# ZynqPS.net
KiCad netlist of a schematic drawn in Altium Designer
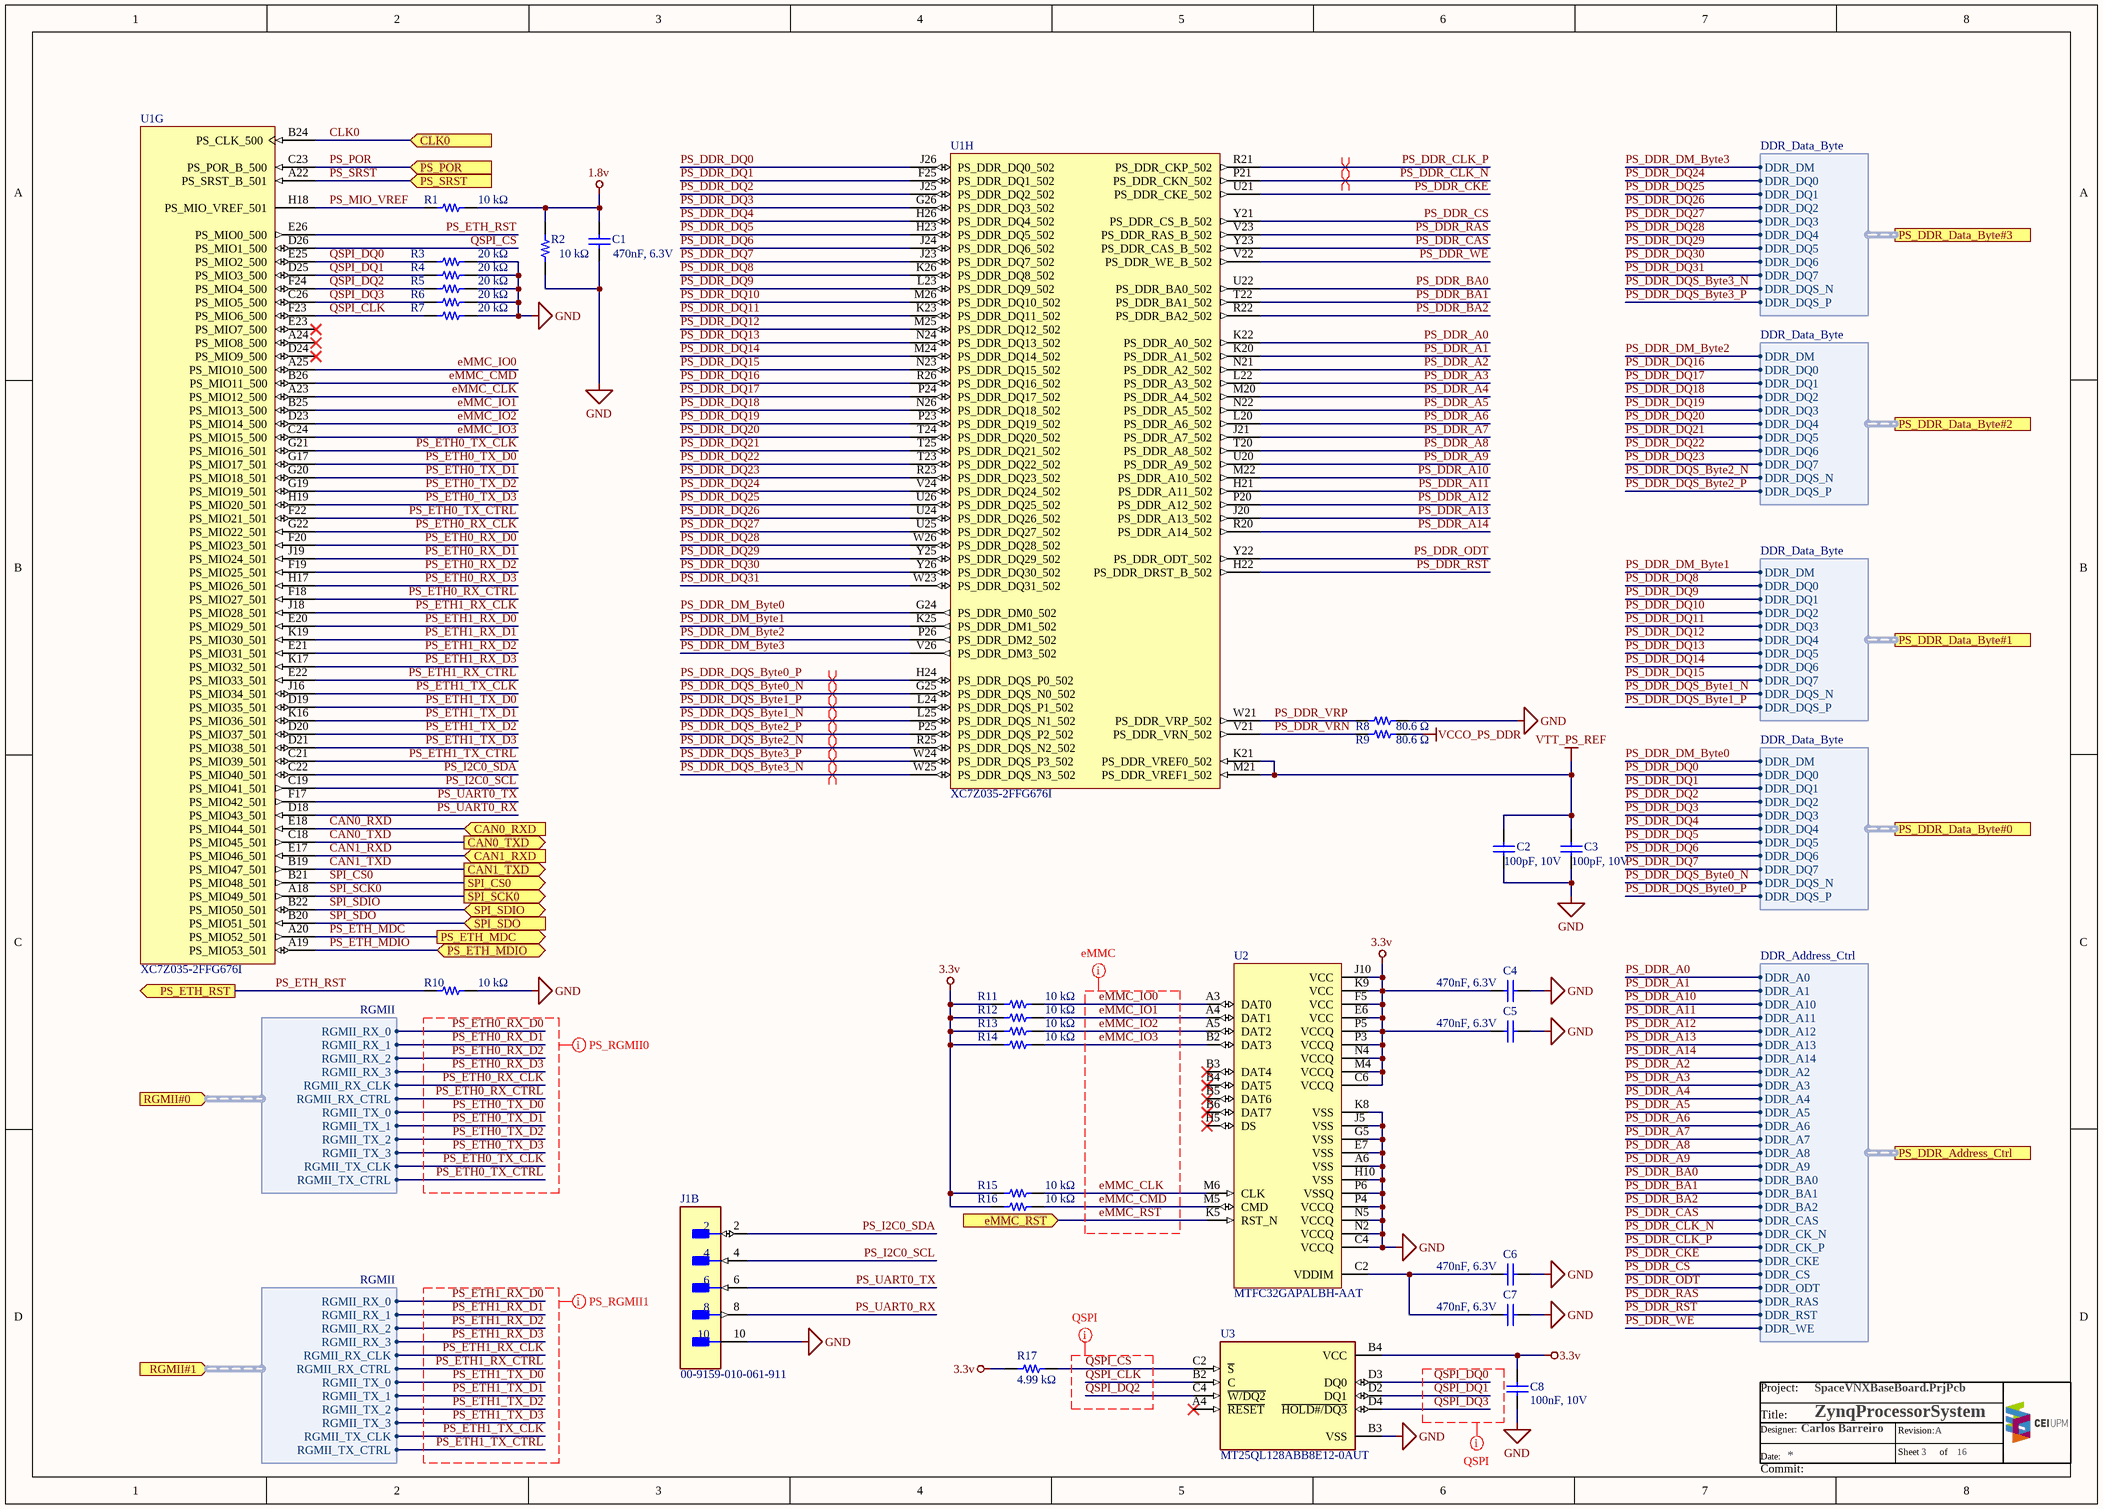
[diagram p0: ZynqPS.SchDoc]

(export (version "E")
  (design (tool "Eeschema 10.0.6"))
  (components
    (comp (ref "C1")
      (value "470nF, 6.3V")
      (footprint "WURTH_WCAP-CSGP_0402")
      (description "WCAP-CSGP Multilayer Ceramic Chip Capacitor, General Purpose, size 0402, X5R, 470nF, 6.3V")
      (fields
        (field (name "MANUFACTURER PART NUMBER") "885012105004")
        (field (name "MANUFACTURER") "Wurth Elektronik")
      )
      (libsource (lib "SpaceVNX") (part "885012105004"))
    )
    (comp (ref "C2")
      (value "100pF, 10V")
      (footprint "WURTH_WCAP-CSGP_0402")
      (description "WCAP-CSGP Multilayer Ceramic Chip Capacitor, General Purpose, size 0402, NP0, 100pF, 10V")
      (fields
        (field (name "MANUFACTURER PART NUMBER") "885012005013")
        (field (name "MANUFACTURER") "Wurth Elektronik")
      )
      (libsource (lib "SpaceVNX") (part "885012005013"))
    )
    (comp (ref "C3")
      (value "100pF, 10V")
      (footprint "WURTH_WCAP-CSGP_0402")
      (description "WCAP-CSGP Multilayer Ceramic Chip Capacitor, General Purpose, size 0402, NP0, 100pF, 10V")
      (fields
        (field (name "MANUFACTURER PART NUMBER") "885012005013")
        (field (name "MANUFACTURER") "Wurth Elektronik")
      )
      (libsource (lib "SpaceVNX") (part "885012005013"))
    )
    (comp (ref "C4")
      (value "470nF, 6.3V")
      (footprint "WURTH_WCAP-CSGP_0402")
      (description "WCAP-CSGP Multilayer Ceramic Chip Capacitor, General Purpose, size 0402, X5R, 470nF, 6.3V")
      (fields
        (field (name "MANUFACTURER PART NUMBER") "885012105004")
        (field (name "MANUFACTURER") "Wurth Elektronik")
      )
      (libsource (lib "SpaceVNX") (part "885012105004"))
    )
    (comp (ref "C5")
      (value "470nF, 6.3V")
      (footprint "WURTH_WCAP-CSGP_0402")
      (description "WCAP-CSGP Multilayer Ceramic Chip Capacitor, General Purpose, size 0402, X5R, 470nF, 6.3V")
      (fields
        (field (name "MANUFACTURER PART NUMBER") "885012105004")
        (field (name "MANUFACTURER") "Wurth Elektronik")
      )
      (libsource (lib "SpaceVNX") (part "885012105004"))
    )
    (comp (ref "C6")
      (value "470nF, 6.3V")
      (footprint "WURTH_WCAP-CSGP_0402")
      (description "WCAP-CSGP Multilayer Ceramic Chip Capacitor, General Purpose, size 0402, X5R, 470nF, 6.3V")
      (fields
        (field (name "MANUFACTURER PART NUMBER") "885012105004")
        (field (name "MANUFACTURER") "Wurth Elektronik")
      )
      (libsource (lib "SpaceVNX") (part "885012105004"))
    )
    (comp (ref "C7")
      (value "470nF, 6.3V")
      (footprint "WURTH_WCAP-CSGP_0402")
      (description "WCAP-CSGP Multilayer Ceramic Chip Capacitor, General Purpose, size 0402, X5R, 470nF, 6.3V")
      (fields
        (field (name "MANUFACTURER PART NUMBER") "885012105004")
        (field (name "MANUFACTURER") "Wurth Elektronik")
      )
      (libsource (lib "SpaceVNX") (part "885012105004"))
    )
    (comp (ref "C8")
      (value "100nF, 10V")
      (footprint "WURTH_WCAP-CSGP_0402")
      (description "WCAP-CSGP Multilayer Ceramic Chip Capacitor, General Purpose, size 0402, X7R, 100nF, 10V")
      (fields
        (field (name "MANUFACTURER PART NUMBER") "885012205018")
        (field (name "MANUFACTURER") "Wurth Elektronik")
      )
      (libsource (lib "SpaceVNX") (part "885012205018"))
    )
    (comp (ref "J1")
      (value "00-9159-010-061-911")
      (footprint "KYOCERA_00-9159-010-061-911")
      (description "Coplanar Open Ended Card Edge Connector 10 Pin")
      (libsource (lib "SpaceVNX") (part "00-9159-010-061-911"))
    )
    (comp (ref "R1")
      (value "10 kΩ")
      (footprint "PANASONIC_ERJ2G_0402")
      (description "General Purpose Thick Film Chip Resistors")
      (fields (field (name "MANUFACTURER") "Panasonic"))
      (libsource (lib "SpaceVNX") (part "ERJ2RKF1002X"))
    )
    (comp (ref "R2")
      (value "10 kΩ")
      (footprint "PANASONIC_ERJ2G_0402")
      (description "General Purpose Thick Film Chip Resistors")
      (fields (field (name "MANUFACTURER") "Panasonic"))
      (libsource (lib "SpaceVNX") (part "ERJ2RKF1002X"))
    )
    (comp (ref "R3")
      (value "20 kΩ")
      (footprint "PANASONIC_ERJ2G_0402")
      (description "General Purpose Thick Film Chip Resistors")
      (fields (field (name "MANUFACTURER") "Panasonic"))
      (libsource (lib "SpaceVNX") (part "ERJ2RKF2002X"))
    )
    (comp (ref "R4")
      (value "20 kΩ")
      (footprint "PANASONIC_ERJ2G_0402")
      (description "General Purpose Thick Film Chip Resistors")
      (fields (field (name "MANUFACTURER") "Panasonic"))
      (libsource (lib "SpaceVNX") (part "ERJ2RKF2002X"))
    )
    (comp (ref "R5")
      (value "20 kΩ")
      (footprint "PANASONIC_ERJ2G_0402")
      (description "General Purpose Thick Film Chip Resistors")
      (fields (field (name "MANUFACTURER") "Panasonic"))
      (libsource (lib "SpaceVNX") (part "ERJ2RKF2002X"))
    )
    (comp (ref "R6")
      (value "20 kΩ")
      (footprint "PANASONIC_ERJ2G_0402")
      (description "General Purpose Thick Film Chip Resistors")
      (fields (field (name "MANUFACTURER") "Panasonic"))
      (libsource (lib "SpaceVNX") (part "ERJ2RKF2002X"))
    )
    (comp (ref "R7")
      (value "20 kΩ")
      (footprint "PANASONIC_ERJ2G_0402")
      (description "General Purpose Thick Film Chip Resistors")
      (fields (field (name "MANUFACTURER") "Panasonic"))
      (libsource (lib "SpaceVNX") (part "ERJ2RKF2002X"))
    )
    (comp (ref "R8")
      (value "80.6 Ω")
      (footprint "PANASONIC_ERJ2G_0402")
      (description "General Purpose Thick Film Chip Resistors")
      (fields (field (name "MANUFACTURER") "Panasonic"))
      (libsource (lib "SpaceVNX") (part "ERJ2RKF80R6X"))
    )
    (comp (ref "R9")
      (value "80.6 Ω")
      (footprint "PANASONIC_ERJ2G_0402")
      (description "General Purpose Thick Film Chip Resistors")
      (fields (field (name "MANUFACTURER") "Panasonic"))
      (libsource (lib "SpaceVNX") (part "ERJ2RKF80R6X"))
    )
    (comp (ref "R10")
      (value "10 kΩ")
      (footprint "PANASONIC_ERJ2G_0402")
      (description "General Purpose Thick Film Chip Resistors")
      (fields (field (name "MANUFACTURER") "Panasonic"))
      (libsource (lib "SpaceVNX") (part "ERJ2RKF1002X"))
    )
    (comp (ref "R11")
      (value "10 kΩ")
      (footprint "PANASONIC_ERJ2G_0402")
      (description "General Purpose Thick Film Chip Resistors")
      (fields (field (name "MANUFACTURER") "Panasonic"))
      (libsource (lib "SpaceVNX") (part "ERJ2RKF1002X"))
    )
    (comp (ref "R12")
      (value "10 kΩ")
      (footprint "PANASONIC_ERJ2G_0402")
      (description "General Purpose Thick Film Chip Resistors")
      (fields (field (name "MANUFACTURER") "Panasonic"))
      (libsource (lib "SpaceVNX") (part "ERJ2RKF1002X"))
    )
    (comp (ref "R13")
      (value "10 kΩ")
      (footprint "PANASONIC_ERJ2G_0402")
      (description "General Purpose Thick Film Chip Resistors")
      (fields (field (name "MANUFACTURER") "Panasonic"))
      (libsource (lib "SpaceVNX") (part "ERJ2RKF1002X"))
    )
    (comp (ref "R14")
      (value "10 kΩ")
      (footprint "PANASONIC_ERJ2G_0402")
      (description "General Purpose Thick Film Chip Resistors")
      (fields (field (name "MANUFACTURER") "Panasonic"))
      (libsource (lib "SpaceVNX") (part "ERJ2RKF1002X"))
    )
    (comp (ref "R15")
      (value "10 kΩ")
      (footprint "PANASONIC_ERJ2G_0402")
      (description "General Purpose Thick Film Chip Resistors")
      (fields (field (name "MANUFACTURER") "Panasonic"))
      (libsource (lib "SpaceVNX") (part "ERJ2RKF1002X"))
    )
    (comp (ref "R16")
      (value "10 kΩ")
      (footprint "PANASONIC_ERJ2G_0402")
      (description "General Purpose Thick Film Chip Resistors")
      (fields (field (name "MANUFACTURER") "Panasonic"))
      (libsource (lib "SpaceVNX") (part "ERJ2RKF1002X"))
    )
    (comp (ref "R17")
      (value "4.99 kΩ")
      (footprint "PANASONIC_ERJ2G_0402")
      (description "General Purpose Thick Film Chip Resistors")
      (fields (field (name "MANUFACTURER") "Panasonic"))
      (libsource (lib "SpaceVNX") (part "ERJ2RKF4991X"))
    )
    (comp (ref "U1")
      (value "XC7Z035-2FFG676I")
      (footprint "XILINX_FBG676")
      (fields (field (name "PARTNUMBER") "XC7Z035-2FBG676I") (field (name "GENERIC PART NUMBER") "XC7Z035"))
      (libsource (lib "SpaceVNX") (part "XC7Z035-2FFG676I"))
    )
    (comp (ref "U2")
      (value "MTFC32GAPALBH-AAT")
      (footprint "Micron_BH")
      (description "Flash Memory Managed NAND e.MMC Automotive 32GB")
      (fields (field (name "MF") "Micron Technology"))
      (libsource (lib "SpaceVNX") (part "MTFC32GAPALBH-AAT"))
    )
    (comp (ref "U3")
      (value "MT25QL128ABB8E12-0AUT")
      (footprint "Micron_RW")
      (description "NOR Serial Flash Memory 128Mb 3.3V Multiple I/O Automotive")
      (fields (field (name "MF") "Micron Technology"))
      (libsource (lib "SpaceVNX") (part "MT25QL128ABB8E12-0AUT"))
    )
  )
  (nets
    (net (code "4") (name "/CAN0_RXD") (class "Default")
      (node (ref "U1") (pin "E18") (pinfunction "PS_MIO44_501_E18") (pintype "input"))
    )
    (net (code "5") (name "/CAN0_TXD") (class "Default")
      (node (ref "U1") (pin "C18") (pinfunction "PS_MIO45_501_C18") (pintype "output"))
    )
    (net (code "6") (name "/CAN1_RXD") (class "Default")
      (node (ref "U1") (pin "E17") (pinfunction "PS_MIO46_501_E17") (pintype "input"))
    )
    (net (code "7") (name "/CAN1_TXD") (class "Default")
      (node (ref "U1") (pin "B19") (pinfunction "PS_MIO47_501_B19") (pintype "output"))
    )
    (net (code "8") (name "/CLK0") (class "Default")
      (node (ref "U1") (pin "B24") (pinfunction "PS_CLK_500_B24") (pintype "input"))
    )
    (net (code "9") (name "/PS_DDR_A0") (class "Default")
      (node (ref "U1") (pin "K22") (pinfunction "PS_DDR_A0_502_K22") (pintype "output"))
    )
    (net (code "10") (name "/PS_DDR_A1") (class "Default")
      (node (ref "U1") (pin "K20") (pinfunction "PS_DDR_A1_502_K20") (pintype "output"))
    )
    (net (code "11") (name "/PS_DDR_A2") (class "Default")
      (node (ref "U1") (pin "N21") (pinfunction "PS_DDR_A2_502_N21") (pintype "output"))
    )
    (net (code "12") (name "/PS_DDR_A3") (class "Default")
      (node (ref "U1") (pin "L22") (pinfunction "PS_DDR_A3_502_L22") (pintype "output"))
    )
    (net (code "13") (name "/PS_DDR_A4") (class "Default")
      (node (ref "U1") (pin "M20") (pinfunction "PS_DDR_A4_502_M20") (pintype "output"))
    )
    (net (code "14") (name "/PS_DDR_A5") (class "Default")
      (node (ref "U1") (pin "N22") (pinfunction "PS_DDR_A5_502_N22") (pintype "output"))
    )
    (net (code "15") (name "/PS_DDR_A6") (class "Default")
      (node (ref "U1") (pin "L20") (pinfunction "PS_DDR_A6_502_L20") (pintype "output"))
    )
    (net (code "16") (name "/PS_DDR_A7") (class "Default")
      (node (ref "U1") (pin "J21") (pinfunction "PS_DDR_A7_502_J21") (pintype "output"))
    )
    (net (code "17") (name "/PS_DDR_A8") (class "Default")
      (node (ref "U1") (pin "T20") (pinfunction "PS_DDR_A8_502_T20") (pintype "output"))
    )
    (net (code "18") (name "/PS_DDR_A9") (class "Default")
      (node (ref "U1") (pin "U20") (pinfunction "PS_DDR_A9_502_U20") (pintype "output"))
    )
    (net (code "19") (name "/PS_DDR_A10") (class "Default")
      (node (ref "U1") (pin "M22") (pinfunction "PS_DDR_A10_502_M22") (pintype "output"))
    )
    (net (code "20") (name "/PS_DDR_A11") (class "Default")
      (node (ref "U1") (pin "H21") (pinfunction "PS_DDR_A11_502_H21") (pintype "output"))
    )
    (net (code "21") (name "/PS_DDR_A12") (class "Default")
      (node (ref "U1") (pin "P20") (pinfunction "PS_DDR_A12_502_P20") (pintype "output"))
    )
    (net (code "22") (name "/PS_DDR_A13") (class "Default")
      (node (ref "U1") (pin "J20") (pinfunction "PS_DDR_A13_502_J20") (pintype "output"))
    )
    (net (code "23") (name "/PS_DDR_A14") (class "Default")
      (node (ref "U1") (pin "R20") (pinfunction "PS_DDR_A14_502_R20") (pintype "output"))
    )
    (net (code "24") (name "/PS_DDR_BA0") (class "Default")
      (node (ref "U1") (pin "U22") (pinfunction "PS_DDR_BA0_502_U22") (pintype "output"))
    )
    (net (code "25") (name "/PS_DDR_BA1") (class "Default")
      (node (ref "U1") (pin "T22") (pinfunction "PS_DDR_BA1_502_T22") (pintype "output"))
    )
    (net (code "26") (name "/PS_DDR_BA2") (class "Default")
      (node (ref "U1") (pin "R22") (pinfunction "PS_DDR_BA2_502_R22") (pintype "output"))
    )
    (net (code "27") (name "/PS_DDR_CAS") (class "Default")
      (node (ref "U1") (pin "Y23") (pinfunction "PS_DDR_CAS_B_502_Y23") (pintype "output"))
    )
    (net (code "28") (name "/PS_DDR_CKE") (class "Default")
      (node (ref "U1") (pin "U21") (pinfunction "PS_DDR_CKE_502_U21") (pintype "output"))
    )
    (net (code "29") (name "/PS_DDR_CLK_N") (class "Default")
      (node (ref "U1") (pin "P21") (pinfunction "PS_DDR_CKN_502_P21") (pintype "output"))
    )
    (net (code "30") (name "/PS_DDR_CLK_P") (class "Default")
      (node (ref "U1") (pin "R21") (pinfunction "PS_DDR_CKP_502_R21") (pintype "output"))
    )
    (net (code "31") (name "/PS_DDR_CS") (class "Default")
      (node (ref "U1") (pin "Y21") (pinfunction "PS_DDR_CS_B_502_Y21") (pintype "output"))
    )
    (net (code "32") (name "/PS_DDR_DM_Byte0") (class "Default")
      (node (ref "U1") (pin "G24") (pinfunction "PS_DDR_DM0_502_G24") (pintype "output"))
    )
    (net (code "33") (name "/PS_DDR_DM_Byte1") (class "Default")
      (node (ref "U1") (pin "K25") (pinfunction "PS_DDR_DM1_502_K25") (pintype "output"))
    )
    (net (code "34") (name "/PS_DDR_DM_Byte2") (class "Default")
      (node (ref "U1") (pin "P26") (pinfunction "PS_DDR_DM2_502_P26") (pintype "output"))
    )
    (net (code "35") (name "/PS_DDR_DM_Byte3") (class "Default")
      (node (ref "U1") (pin "V26") (pinfunction "PS_DDR_DM3_502_V26") (pintype "output"))
    )
    (net (code "36") (name "/PS_DDR_DQ0") (class "Default")
      (node (ref "U1") (pin "J26") (pinfunction "PS_DDR_DQ0_502_J26") (pintype "bidirectional"))
    )
    (net (code "37") (name "/PS_DDR_DQ1") (class "Default")
      (node (ref "U1") (pin "F25") (pinfunction "PS_DDR_DQ1_502_F25") (pintype "bidirectional"))
    )
    (net (code "38") (name "/PS_DDR_DQ2") (class "Default")
      (node (ref "U1") (pin "J25") (pinfunction "PS_DDR_DQ2_502_J25") (pintype "bidirectional"))
    )
    (net (code "39") (name "/PS_DDR_DQ3") (class "Default")
      (node (ref "U1") (pin "G26") (pinfunction "PS_DDR_DQ3_502_G26") (pintype "bidirectional"))
    )
    (net (code "40") (name "/PS_DDR_DQ4") (class "Default")
      (node (ref "U1") (pin "H26") (pinfunction "PS_DDR_DQ4_502_H26") (pintype "bidirectional"))
    )
    (net (code "41") (name "/PS_DDR_DQ5") (class "Default")
      (node (ref "U1") (pin "H23") (pinfunction "PS_DDR_DQ5_502_H23") (pintype "bidirectional"))
    )
    (net (code "42") (name "/PS_DDR_DQ6") (class "Default")
      (node (ref "U1") (pin "J24") (pinfunction "PS_DDR_DQ6_502_J24") (pintype "bidirectional"))
    )
    (net (code "43") (name "/PS_DDR_DQ7") (class "Default")
      (node (ref "U1") (pin "J23") (pinfunction "PS_DDR_DQ7_502_J23") (pintype "bidirectional"))
    )
    (net (code "44") (name "/PS_DDR_DQ8") (class "Default")
      (node (ref "U1") (pin "K26") (pinfunction "PS_DDR_DQ8_502_K26") (pintype "bidirectional"))
    )
    (net (code "45") (name "/PS_DDR_DQ9") (class "Default")
      (node (ref "U1") (pin "L23") (pinfunction "PS_DDR_DQ9_502_L23") (pintype "bidirectional"))
    )
    (net (code "46") (name "/PS_DDR_DQ10") (class "Default")
      (node (ref "U1") (pin "M26") (pinfunction "PS_DDR_DQ10_502_M26") (pintype "bidirectional"))
    )
    (net (code "47") (name "/PS_DDR_DQ11") (class "Default")
      (node (ref "U1") (pin "K23") (pinfunction "PS_DDR_DQ11_502_K23") (pintype "bidirectional"))
    )
    (net (code "48") (name "/PS_DDR_DQ12") (class "Default")
      (node (ref "U1") (pin "M25") (pinfunction "PS_DDR_DQ12_502_M25") (pintype "bidirectional"))
    )
    (net (code "49") (name "/PS_DDR_DQ13") (class "Default")
      (node (ref "U1") (pin "N24") (pinfunction "PS_DDR_DQ13_502_N24") (pintype "bidirectional"))
    )
    (net (code "50") (name "/PS_DDR_DQ14") (class "Default")
      (node (ref "U1") (pin "M24") (pinfunction "PS_DDR_DQ14_502_M24") (pintype "bidirectional"))
    )
    (net (code "51") (name "/PS_DDR_DQ15") (class "Default")
      (node (ref "U1") (pin "N23") (pinfunction "PS_DDR_DQ15_502_N23") (pintype "bidirectional"))
    )
    (net (code "52") (name "/PS_DDR_DQ16") (class "Default")
      (node (ref "U1") (pin "R26") (pinfunction "PS_DDR_DQ16_502_R26") (pintype "bidirectional"))
    )
    (net (code "53") (name "/PS_DDR_DQ17") (class "Default")
      (node (ref "U1") (pin "P24") (pinfunction "PS_DDR_DQ17_502_P24") (pintype "bidirectional"))
    )
    (net (code "54") (name "/PS_DDR_DQ18") (class "Default")
      (node (ref "U1") (pin "N26") (pinfunction "PS_DDR_DQ18_502_N26") (pintype "bidirectional"))
    )
    (net (code "55") (name "/PS_DDR_DQ19") (class "Default")
      (node (ref "U1") (pin "P23") (pinfunction "PS_DDR_DQ19_502_P23") (pintype "bidirectional"))
    )
    (net (code "56") (name "/PS_DDR_DQ20") (class "Default")
      (node (ref "U1") (pin "T24") (pinfunction "PS_DDR_DQ20_502_T24") (pintype "bidirectional"))
    )
    (net (code "57") (name "/PS_DDR_DQ21") (class "Default")
      (node (ref "U1") (pin "T25") (pinfunction "PS_DDR_DQ21_502_T25") (pintype "bidirectional"))
    )
    (net (code "58") (name "/PS_DDR_DQ22") (class "Default")
      (node (ref "U1") (pin "T23") (pinfunction "PS_DDR_DQ22_502_T23") (pintype "bidirectional"))
    )
    (net (code "59") (name "/PS_DDR_DQ23") (class "Default")
      (node (ref "U1") (pin "R23") (pinfunction "PS_DDR_DQ23_502_R23") (pintype "bidirectional"))
    )
    (net (code "60") (name "/PS_DDR_DQ24") (class "Default")
      (node (ref "U1") (pin "V24") (pinfunction "PS_DDR_DQ24_502_V24") (pintype "bidirectional"))
    )
    (net (code "61") (name "/PS_DDR_DQ25") (class "Default")
      (node (ref "U1") (pin "U26") (pinfunction "PS_DDR_DQ25_502_U26") (pintype "bidirectional"))
    )
    (net (code "62") (name "/PS_DDR_DQ26") (class "Default")
      (node (ref "U1") (pin "U24") (pinfunction "PS_DDR_DQ26_502_U24") (pintype "bidirectional"))
    )
    (net (code "63") (name "/PS_DDR_DQ27") (class "Default")
      (node (ref "U1") (pin "U25") (pinfunction "PS_DDR_DQ27_502_U25") (pintype "bidirectional"))
    )
    (net (code "64") (name "/PS_DDR_DQ28") (class "Default")
      (node (ref "U1") (pin "W26") (pinfunction "PS_DDR_DQ28_502_W26") (pintype "bidirectional"))
    )
    (net (code "65") (name "/PS_DDR_DQ29") (class "Default")
      (node (ref "U1") (pin "Y25") (pinfunction "PS_DDR_DQ29_502_Y25") (pintype "bidirectional"))
    )
    (net (code "66") (name "/PS_DDR_DQ30") (class "Default")
      (node (ref "U1") (pin "Y26") (pinfunction "PS_DDR_DQ30_502_Y26") (pintype "bidirectional"))
    )
    (net (code "67") (name "/PS_DDR_DQ31") (class "Default")
      (node (ref "U1") (pin "W23") (pinfunction "PS_DDR_DQ31_502_W23") (pintype "bidirectional"))
    )
    (net (code "68") (name "/PS_DDR_DQS_Byte0_N") (class "Default")
      (node (ref "U1") (pin "G25") (pinfunction "PS_DDR_DQS_N0_502_G25") (pintype "bidirectional"))
    )
    (net (code "69") (name "/PS_DDR_DQS_Byte0_P") (class "Default")
      (node (ref "U1") (pin "H24") (pinfunction "PS_DDR_DQS_P0_502_H24") (pintype "bidirectional"))
    )
    (net (code "70") (name "/PS_DDR_DQS_Byte1_N") (class "Default")
      (node (ref "U1") (pin "L25") (pinfunction "PS_DDR_DQS_N1_502_L25") (pintype "bidirectional"))
    )
    (net (code "71") (name "/PS_DDR_DQS_Byte1_P") (class "Default")
      (node (ref "U1") (pin "L24") (pinfunction "PS_DDR_DQS_P1_502_L24") (pintype "bidirectional"))
    )
    (net (code "72") (name "/PS_DDR_DQS_Byte2_N") (class "Default")
      (node (ref "U1") (pin "R25") (pinfunction "PS_DDR_DQS_N2_502_R25") (pintype "bidirectional"))
    )
    (net (code "73") (name "/PS_DDR_DQS_Byte2_P") (class "Default")
      (node (ref "U1") (pin "P25") (pinfunction "PS_DDR_DQS_P2_502_P25") (pintype "bidirectional"))
    )
    (net (code "74") (name "/PS_DDR_DQS_Byte3_N") (class "Default")
      (node (ref "U1") (pin "W25") (pinfunction "PS_DDR_DQS_N3_502_W25") (pintype "bidirectional"))
    )
    (net (code "75") (name "/PS_DDR_DQS_Byte3_P") (class "Default")
      (node (ref "U1") (pin "W24") (pinfunction "PS_DDR_DQS_P3_502_W24") (pintype "bidirectional"))
    )
    (net (code "76") (name "/PS_DDR_ODT") (class "Default")
      (node (ref "U1") (pin "Y22") (pinfunction "PS_DDR_ODT_502_Y22") (pintype "output"))
    )
    (net (code "77") (name "/PS_DDR_RAS") (class "Default")
      (node (ref "U1") (pin "V23") (pinfunction "PS_DDR_RAS_B_502_V23") (pintype "output"))
    )
    (net (code "78") (name "/PS_DDR_RST") (class "Default")
      (node (ref "U1") (pin "H22") (pinfunction "PS_DDR_DRST_B_502_H22") (pintype "output"))
    )
    (net (code "79") (name "/PS_DDR_VRN") (class "Default")
      (node (ref "R9") (pin "1") (pinfunction "1_1") (pintype "passive"))
      (node (ref "U1") (pin "V21") (pinfunction "PS_DDR_VRN_502_V21") (pintype "output"))
    )
    (net (code "80") (name "/PS_DDR_VRP") (class "Default")
      (node (ref "R8") (pin "1") (pinfunction "1_1") (pintype "passive"))
      (node (ref "U1") (pin "W21") (pinfunction "PS_DDR_VRP_502_W21") (pintype "output"))
    )
    (net (code "81") (name "/PS_DDR_WE") (class "Default")
      (node (ref "U1") (pin "V22") (pinfunction "PS_DDR_WE_B_502_V22") (pintype "output"))
    )
    (net (code "82") (name "/PS_ETH0_RX_CLK") (class "Default")
      (node (ref "U1") (pin "G22") (pinfunction "PS_MIO22_501_G22") (pintype "input"))
    )
    (net (code "83") (name "/PS_ETH0_RX_CTRL") (class "Default")
      (node (ref "U1") (pin "F18") (pinfunction "PS_MIO27_501_F18") (pintype "input"))
    )
    (net (code "84") (name "/PS_ETH0_RX_D0") (class "Default")
      (node (ref "U1") (pin "F20") (pinfunction "PS_MIO23_501_F20") (pintype "input"))
    )
    (net (code "85") (name "/PS_ETH0_RX_D1") (class "Default")
      (node (ref "U1") (pin "J19") (pinfunction "PS_MIO24_501_J19") (pintype "input"))
    )
    (net (code "86") (name "/PS_ETH0_RX_D2") (class "Default")
      (node (ref "U1") (pin "F19") (pinfunction "PS_MIO25_501_F19") (pintype "input"))
    )
    (net (code "87") (name "/PS_ETH0_RX_D3") (class "Default")
      (node (ref "U1") (pin "H17") (pinfunction "PS_MIO26_501_H17") (pintype "input"))
    )
    (net (code "88") (name "/PS_ETH0_TX_CLK") (class "Default")
      (node (ref "U1") (pin "G21") (pinfunction "PS_MIO16_501_G21") (pintype "bidirectional"))
    )
    (net (code "89") (name "/PS_ETH0_TX_CTRL") (class "Default")
      (node (ref "U1") (pin "F22") (pinfunction "PS_MIO21_501_F22") (pintype "bidirectional"))
    )
    (net (code "90") (name "/PS_ETH0_TX_D0") (class "Default")
      (node (ref "U1") (pin "G17") (pinfunction "PS_MIO17_501_G17") (pintype "bidirectional"))
    )
    (net (code "91") (name "/PS_ETH0_TX_D1") (class "Default")
      (node (ref "U1") (pin "G20") (pinfunction "PS_MIO18_501_G20") (pintype "bidirectional"))
    )
    (net (code "92") (name "/PS_ETH0_TX_D2") (class "Default")
      (node (ref "U1") (pin "G19") (pinfunction "PS_MIO19_501_G19") (pintype "bidirectional"))
    )
    (net (code "93") (name "/PS_ETH0_TX_D3") (class "Default")
      (node (ref "U1") (pin "H19") (pinfunction "PS_MIO20_501_H19") (pintype "bidirectional"))
    )
    (net (code "94") (name "/PS_ETH1_RX_CLK") (class "Default")
      (node (ref "U1") (pin "J18") (pinfunction "PS_MIO28_501_J18") (pintype "input"))
    )
    (net (code "95") (name "/PS_ETH1_RX_CTRL") (class "Default")
      (node (ref "U1") (pin "E22") (pinfunction "PS_MIO33_501_E22") (pintype "input"))
    )
    (net (code "96") (name "/PS_ETH1_RX_D0") (class "Default")
      (node (ref "U1") (pin "E20") (pinfunction "PS_MIO29_501_E20") (pintype "input"))
    )
    (net (code "97") (name "/PS_ETH1_RX_D1") (class "Default")
      (node (ref "U1") (pin "K19") (pinfunction "PS_MIO30_501_K19") (pintype "input"))
    )
    (net (code "98") (name "/PS_ETH1_RX_D2") (class "Default")
      (node (ref "U1") (pin "E21") (pinfunction "PS_MIO31_501_E21") (pintype "input"))
    )
    (net (code "99") (name "/PS_ETH1_RX_D3") (class "Default")
      (node (ref "U1") (pin "K17") (pinfunction "PS_MIO32_501_K17") (pintype "input"))
    )
    (net (code "100") (name "/PS_ETH1_TX_CLK") (class "Default")
      (node (ref "U1") (pin "J16") (pinfunction "PS_MIO34_501_J16") (pintype "bidirectional"))
    )
    (net (code "101") (name "/PS_ETH1_TX_CTRL") (class "Default")
      (node (ref "U1") (pin "C21") (pinfunction "PS_MIO39_501_C21") (pintype "bidirectional"))
    )
    (net (code "102") (name "/PS_ETH1_TX_D0") (class "Default")
      (node (ref "U1") (pin "D19") (pinfunction "PS_MIO35_501_D19") (pintype "bidirectional"))
    )
    (net (code "103") (name "/PS_ETH1_TX_D1") (class "Default")
      (node (ref "U1") (pin "K16") (pinfunction "PS_MIO36_501_K16") (pintype "bidirectional"))
    )
    (net (code "104") (name "/PS_ETH1_TX_D2") (class "Default")
      (node (ref "U1") (pin "D20") (pinfunction "PS_MIO37_501_D20") (pintype "bidirectional"))
    )
    (net (code "105") (name "/PS_ETH1_TX_D3") (class "Default")
      (node (ref "U1") (pin "D21") (pinfunction "PS_MIO38_501_D21") (pintype "bidirectional"))
    )
    (net (code "106") (name "/PS_ETH_MDC") (class "Default")
      (node (ref "U1") (pin "A20") (pinfunction "PS_MIO52_501_A20") (pintype "output"))
    )
    (net (code "107") (name "/PS_ETH_MDIO") (class "Default")
      (node (ref "U1") (pin "A19") (pinfunction "PS_MIO53_501_A19") (pintype "bidirectional"))
    )
    (net (code "108") (name "/PS_ETH_RST") (class "Default")
      (node (ref "R10") (pin "2") (pinfunction "2_2") (pintype "passive"))
      (node (ref "U1") (pin "E26") (pinfunction "PS_MIO0_500_E26") (pintype "output"))
    )
    (net (code "109") (name "/PS_I2C0_SCL") (class "Default")
      (node (ref "J1") (pin "4") (pinfunction "4_4") (pintype "input"))
      (node (ref "U1") (pin "C19") (pinfunction "PS_MIO41_501_C19") (pintype "output"))
    )
    (net (code "110") (name "/PS_I2C0_SDA") (class "Default")
      (node (ref "J1") (pin "2") (pinfunction "2_2") (pintype "bidirectional"))
      (node (ref "U1") (pin "C22") (pinfunction "PS_MIO40_501_C22") (pintype "bidirectional"))
    )
    (net (code "111") (name "/PS_MIO_VREF") (class "Default")
      (node (ref "R1") (pin "2") (pinfunction "2_2") (pintype "passive"))
      (node (ref "U1") (pin "H18") (pinfunction "PS_MIO_VREF_501_H18") (pintype "passive"))
    )
    (net (code "112") (name "/PS_POR") (class "Default")
      (node (ref "U1") (pin "C23") (pinfunction "PS_POR_B_500_C23") (pintype "input"))
    )
    (net (code "113") (name "/PS_SRST") (class "Default")
      (node (ref "U1") (pin "A22") (pinfunction "PS_SRST_B_501_A22") (pintype "input"))
    )
    (net (code "114") (name "/PS_UART0_RX") (class "Default")
      (node (ref "J1") (pin "8") (pinfunction "8_8") (pintype "output"))
      (node (ref "U1") (pin "D18") (pinfunction "PS_MIO43_501_D18") (pintype "input"))
    )
    (net (code "115") (name "/PS_UART0_TX") (class "Default")
      (node (ref "J1") (pin "6") (pinfunction "6_6") (pintype "input"))
      (node (ref "U1") (pin "F17") (pinfunction "PS_MIO42_501_F17") (pintype "output"))
    )
    (net (code "116") (name "/QSPI_CLK") (class "Default")
      (node (ref "R7") (pin "1") (pinfunction "1_1") (pintype "passive"))
      (node (ref "U1") (pin "F23") (pinfunction "PS_MIO6_500_F23") (pintype "bidirectional"))
      (node (ref "U3") (pin "B2") (pinfunction "C_B2") (pintype "input"))
    )
    (net (code "117") (name "/QSPI_CS") (class "Default")
      (node (ref "R17") (pin "2") (pinfunction "2_2") (pintype "passive"))
      (node (ref "U1") (pin "D26") (pinfunction "PS_MIO1_500_D26") (pintype "bidirectional"))
      (node (ref "U3") (pin "C2") (pinfunction "~{S}_C2") (pintype "input"))
    )
    (net (code "118") (name "/QSPI_DQ0") (class "Default")
      (node (ref "R3") (pin "1") (pinfunction "1_1") (pintype "passive"))
      (node (ref "U1") (pin "E25") (pinfunction "PS_MIO2_500_E25") (pintype "bidirectional"))
      (node (ref "U3") (pin "D3") (pinfunction "DQ0_D3") (pintype "bidirectional"))
    )
    (net (code "119") (name "/QSPI_DQ1") (class "Default")
      (node (ref "R4") (pin "1") (pinfunction "1_1") (pintype "passive"))
      (node (ref "U1") (pin "D25") (pinfunction "PS_MIO3_500_D25") (pintype "bidirectional"))
      (node (ref "U3") (pin "D2") (pinfunction "DQ1_D2") (pintype "bidirectional"))
    )
    (net (code "120") (name "/QSPI_DQ2") (class "Default")
      (node (ref "R5") (pin "1") (pinfunction "1_1") (pintype "passive"))
      (node (ref "U1") (pin "F24") (pinfunction "PS_MIO4_500_F24") (pintype "bidirectional"))
      (node (ref "U3") (pin "C4") (pinfunction "~{W/DQ2}_C4") (pintype "input"))
    )
    (net (code "121") (name "/QSPI_DQ3") (class "Default")
      (node (ref "R6") (pin "1") (pinfunction "1_1") (pintype "passive"))
      (node (ref "U1") (pin "C26") (pinfunction "PS_MIO5_500_C26") (pintype "bidirectional"))
      (node (ref "U3") (pin "D4") (pinfunction "~{HOLD#/DQ3}_D4") (pintype "bidirectional"))
    )
    (net (code "122") (name "/SPI_CS0") (class "Default")
      (node (ref "U1") (pin "B21") (pinfunction "PS_MIO48_501_B21") (pintype "output"))
    )
    (net (code "123") (name "/SPI_SCK0") (class "Default")
      (node (ref "U1") (pin "A18") (pinfunction "PS_MIO49_501_A18") (pintype "output"))
    )
    (net (code "124") (name "/SPI_SDIO") (class "Default")
      (node (ref "U1") (pin "B22") (pinfunction "PS_MIO50_501_B22") (pintype "bidirectional"))
    )
    (net (code "125") (name "/SPI_SDO") (class "Default")
      (node (ref "U1") (pin "B20") (pinfunction "PS_MIO51_501_B20") (pintype "input"))
    )
    (net (code "126") (name "/eMMC_CLK") (class "Default")
      (node (ref "R15") (pin "1") (pinfunction "1_1") (pintype "passive"))
      (node (ref "U1") (pin "A23") (pinfunction "PS_MIO12_500_A23") (pintype "bidirectional"))
      (node (ref "U2") (pin "M6") (pinfunction "CLK_M6") (pintype "input"))
    )
    (net (code "127") (name "/eMMC_CMD") (class "Default")
      (node (ref "R16") (pin "1") (pinfunction "1_1") (pintype "passive"))
      (node (ref "U1") (pin "B26") (pinfunction "PS_MIO11_500_B26") (pintype "bidirectional"))
      (node (ref "U2") (pin "M5") (pinfunction "CMD_M5") (pintype "bidirectional"))
    )
    (net (code "128") (name "/eMMC_IO0") (class "Default")
      (node (ref "R11") (pin "1") (pinfunction "1_1") (pintype "passive"))
      (node (ref "U1") (pin "A25") (pinfunction "PS_MIO10_500_A25") (pintype "bidirectional"))
      (node (ref "U2") (pin "A3") (pinfunction "DAT0_A3") (pintype "bidirectional"))
    )
    (net (code "129") (name "/eMMC_IO1") (class "Default")
      (node (ref "R12") (pin "1") (pinfunction "1_1") (pintype "passive"))
      (node (ref "U1") (pin "B25") (pinfunction "PS_MIO13_500_B25") (pintype "bidirectional"))
      (node (ref "U2") (pin "A4") (pinfunction "DAT1_A4") (pintype "bidirectional"))
    )
    (net (code "130") (name "/eMMC_IO2") (class "Default")
      (node (ref "R13") (pin "1") (pinfunction "1_1") (pintype "passive"))
      (node (ref "U1") (pin "D23") (pinfunction "PS_MIO14_500_D23") (pintype "bidirectional"))
      (node (ref "U2") (pin "A5") (pinfunction "DAT2_A5") (pintype "bidirectional"))
    )
    (net (code "131") (name "/eMMC_IO3") (class "Default")
      (node (ref "R14") (pin "1") (pinfunction "1_1") (pintype "passive"))
      (node (ref "U1") (pin "C24") (pinfunction "PS_MIO15_500_C24") (pintype "bidirectional"))
      (node (ref "U2") (pin "B2") (pinfunction "DAT3_B2") (pintype "bidirectional"))
    )
    (net (code "132") (name "/eMMC_RST") (class "Default")
      (node (ref "U2") (pin "K5") (pinfunction "RST_N_K5") (pintype "input"))
    )
    (net (code "136") (name "1.8v") (class "Default")
      (node (ref "C1") (pin "1") (pinfunction "1_1") (pintype "passive"))
      (node (ref "R1") (pin "1") (pinfunction "1_1") (pintype "passive"))
      (node (ref "R2") (pin "2") (pinfunction "2_2") (pintype "passive"))
    )
    (net (code "137") (name "3.3v") (class "Default")
      (node (ref "C4") (pin "1") (pinfunction "1_1") (pintype "passive"))
      (node (ref "C5") (pin "1") (pinfunction "1_1") (pintype "passive"))
      (node (ref "C8") (pin "2") (pinfunction "2_2") (pintype "passive"))
      (node (ref "R11") (pin "2") (pinfunction "2_2") (pintype "passive"))
      (node (ref "R12") (pin "2") (pinfunction "2_2") (pintype "passive"))
      (node (ref "R13") (pin "2") (pinfunction "2_2") (pintype "passive"))
      (node (ref "R14") (pin "2") (pinfunction "2_2") (pintype "passive"))
      (node (ref "R15") (pin "2") (pinfunction "2_2") (pintype "passive"))
      (node (ref "R16") (pin "2") (pinfunction "2_2") (pintype "passive"))
      (node (ref "R17") (pin "1") (pinfunction "1_1") (pintype "passive"))
      (node (ref "U2") (pin "C6") (pinfunction "VCCQ_C6") (pintype "power_in"))
      (node (ref "U2") (pin "E6") (pinfunction "VCC_E6") (pintype "power_in"))
      (node (ref "U2") (pin "F5") (pinfunction "VCC_F5") (pintype "power_in"))
      (node (ref "U2") (pin "J10") (pinfunction "VCC_J10") (pintype "power_in"))
      (node (ref "U2") (pin "K9") (pinfunction "VCC_K9") (pintype "power_in"))
      (node (ref "U2") (pin "M4") (pinfunction "VCCQ_M4") (pintype "power_in"))
      (node (ref "U2") (pin "N4") (pinfunction "VCCQ_N4") (pintype "power_in"))
      (node (ref "U2") (pin "P3") (pinfunction "VCCQ_P3") (pintype "power_in"))
      (node (ref "U2") (pin "P5") (pinfunction "VCCQ_P5") (pintype "power_in"))
      (node (ref "U3") (pin "B4") (pinfunction "VCC_B4") (pintype "power_in"))
    )
    (net (code "138") (name "GND") (class "Default")
      (node (ref "C1") (pin "2") (pinfunction "2_2") (pintype "passive"))
      (node (ref "C2") (pin "1") (pinfunction "1_1") (pintype "passive"))
      (node (ref "C3") (pin "1") (pinfunction "1_1") (pintype "passive"))
      (node (ref "C4") (pin "2") (pinfunction "2_2") (pintype "passive"))
      (node (ref "C5") (pin "2") (pinfunction "2_2") (pintype "passive"))
      (node (ref "C6") (pin "2") (pinfunction "2_2") (pintype "passive"))
      (node (ref "C7") (pin "2") (pinfunction "2_2") (pintype "passive"))
      (node (ref "C8") (pin "1") (pinfunction "1_1") (pintype "passive"))
      (node (ref "J1") (pin "10") (pinfunction "10_10") (pintype "passive"))
      (node (ref "R10") (pin "1") (pinfunction "1_1") (pintype "passive"))
      (node (ref "R2") (pin "1") (pinfunction "1_1") (pintype "passive"))
      (node (ref "R3") (pin "2") (pinfunction "2_2") (pintype "passive"))
      (node (ref "R4") (pin "2") (pinfunction "2_2") (pintype "passive"))
      (node (ref "R5") (pin "2") (pinfunction "2_2") (pintype "passive"))
      (node (ref "R6") (pin "2") (pinfunction "2_2") (pintype "passive"))
      (node (ref "R7") (pin "2") (pinfunction "2_2") (pintype "passive"))
      (node (ref "R8") (pin "2") (pinfunction "2_2") (pintype "passive"))
      (node (ref "U2") (pin "A6") (pinfunction "VSS_A6") (pintype "power_in"))
      (node (ref "U2") (pin "C4") (pinfunction "VCCQ_C4") (pintype "power_in"))
      (node (ref "U2") (pin "E7") (pinfunction "VSS_E7") (pintype "power_in"))
      (node (ref "U2") (pin "G5") (pinfunction "VSS_G5") (pintype "power_in"))
      (node (ref "U2") (pin "H10") (pinfunction "VSS_H10") (pintype "power_in"))
      (node (ref "U2") (pin "J5") (pinfunction "VSS_J5") (pintype "power_in"))
      (node (ref "U2") (pin "K8") (pinfunction "VSS_K8") (pintype "power_in"))
      (node (ref "U2") (pin "N2") (pinfunction "VCCQ_N2") (pintype "power_in"))
      (node (ref "U2") (pin "N5") (pinfunction "VCCQ_N5") (pintype "power_in"))
      (node (ref "U2") (pin "P4") (pinfunction "VCCQ_P4") (pintype "power_in"))
      (node (ref "U2") (pin "P6") (pinfunction "VSSQ_P6") (pintype "power_in"))
      (node (ref "U3") (pin "B3") (pinfunction "VSS_B3") (pintype "power_in"))
    )
    (net (code "139") (name "Net-(U2-VDDIM)") (class "Default")
      (node (ref "C6") (pin "1") (pinfunction "1_1") (pintype "passive"))
      (node (ref "C7") (pin "1") (pinfunction "1_1") (pintype "passive"))
      (node (ref "U2") (pin "C2") (pinfunction "VDDIM_C2") (pintype "power_in"))
    )
    (net (code "140") (name "VCCO_PS_DDR") (class "Default")
      (node (ref "R9") (pin "2") (pinfunction "2_2") (pintype "passive"))
    )
    (net (code "141") (name "VTT_PS_REF") (class "Default")
      (node (ref "C2") (pin "2") (pinfunction "2_2") (pintype "passive"))
      (node (ref "C3") (pin "2") (pinfunction "2_2") (pintype "passive"))
      (node (ref "U1") (pin "K21") (pinfunction "PS_DDR_VREF0_502_K21") (pintype "input"))
      (node (ref "U1") (pin "M21") (pinfunction "PS_DDR_VREF1_502_M21") (pintype "input"))
    )
    (net (code "142") (name "unconnected-(U1G-PS_MIO7_500-PadE23)") (class "Default")
      (node (ref "U1") (pin "E23") (pinfunction "PS_MIO7_500_E23") (pintype "bidirectional+no_connect"))
    )
    (net (code "143") (name "unconnected-(U1G-PS_MIO8_500-PadA24)") (class "Default")
      (node (ref "U1") (pin "A24") (pinfunction "PS_MIO8_500_A24") (pintype "bidirectional+no_connect"))
    )
    (net (code "144") (name "unconnected-(U1G-PS_MIO9_500-PadD24)") (class "Default")
      (node (ref "U1") (pin "D24") (pinfunction "PS_MIO9_500_D24") (pintype "bidirectional+no_connect"))
    )
    (net (code "145") (name "unconnected-(U2-DAT4-PadB3)") (class "Default")
      (node (ref "U2") (pin "B3") (pinfunction "DAT4_B3") (pintype "bidirectional+no_connect"))
    )
    (net (code "146") (name "unconnected-(U2-DAT5-PadB4)") (class "Default")
      (node (ref "U2") (pin "B4") (pinfunction "DAT5_B4") (pintype "bidirectional+no_connect"))
    )
    (net (code "147") (name "unconnected-(U2-DAT6-PadB5)") (class "Default")
      (node (ref "U2") (pin "B5") (pinfunction "DAT6_B5") (pintype "bidirectional+no_connect"))
    )
    (net (code "148") (name "unconnected-(U2-DAT7-PadB6)") (class "Default")
      (node (ref "U2") (pin "B6") (pinfunction "DAT7_B6") (pintype "bidirectional+no_connect"))
    )
    (net (code "149") (name "unconnected-(U2-DS-PadH5)") (class "Default")
      (node (ref "U2") (pin "H5") (pinfunction "DS_H5") (pintype "bidirectional+no_connect"))
    )
    (net (code "150") (name "unconnected-(U3-~{RESET}-PadA4)") (class "Default")
      (node (ref "U3") (pin "A4") (pinfunction "~{RESET}_A4") (pintype "input+no_connect"))
    )
  )
)
